# Schematic.net
KiCad netlist of a schematic drawn in EAGLE
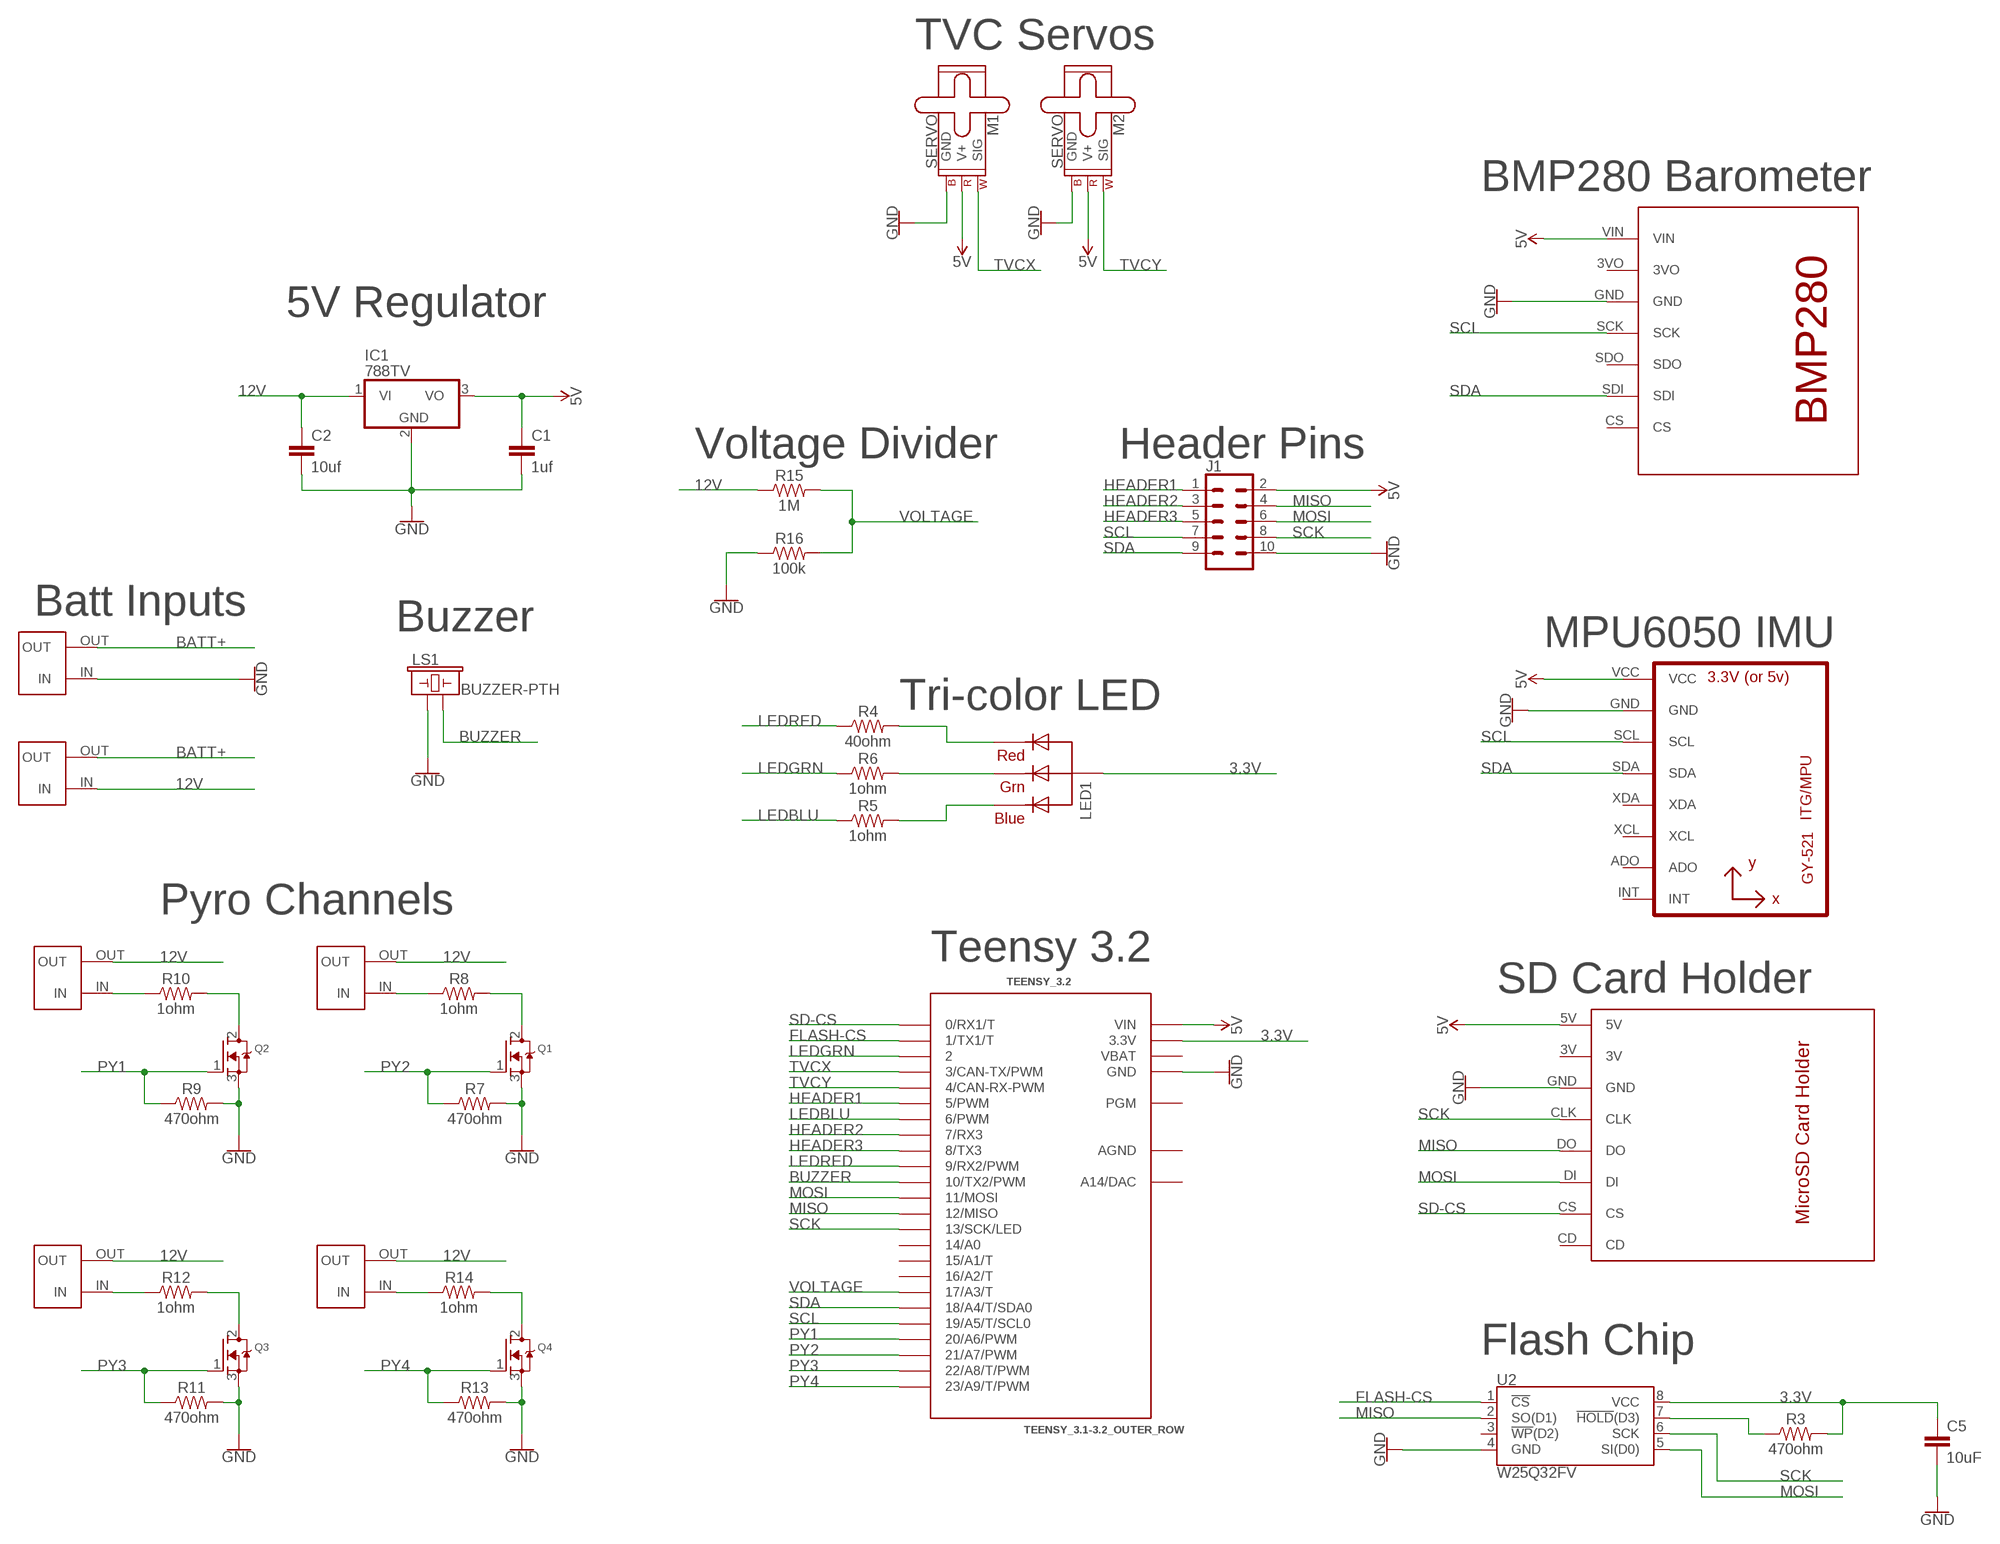
[diagram p0: schematic, sheet 1]

(export (version "E")
  (design (tool "Eeschema 10.0.6"))
  (components
    (comp (ref "C1")
      (value "1uf")
      (footprint "eagle-import:CAP-PTH-2.54")
      (libsource (lib "eagle-import") (part "22PF-PTH-2.54MM-200V-5%"))
    )
    (comp (ref "C2")
      (value "10uf")
      (footprint "eagle-import:CAP-PTH-2.54")
      (libsource (lib "eagle-import") (part "22PF-PTH-2.54MM-200V-5%"))
    )
    (comp (ref "C5")
      (value "10uF")
      (footprint "eagle-import:CAP-PTH-2.54")
      (libsource (lib "eagle-import") (part "22PF-PTH-2.54MM-200V-5%"))
    )
    (comp (ref "IC1")
      (value "788TV")
      (footprint "eagle-import:TO220V")
      (libsource (lib "eagle-import") (part "78TV8"))
    )
    (comp (ref "J1")
      (value "CONN_05X2NO_SILK")
      (footprint "eagle-import:2X5_NOSILK")
      (libsource (lib "eagle-import") (part "CONN_05X2NO_SILK"))
    )
    (comp (ref "LED1")
      (value "RGBLED_CA-5MM")
      (footprint "eagle-import:LED5MMRGB")
      (libsource (lib "eagle-import") (part "RGBLED_CA-5MM"))
    )
    (comp (ref "LS1")
      (value "BUZZER-PTH")
      (footprint "eagle-import:BUZZER-12MM")
      (libsource (lib "eagle-import") (part "BUZZER-PTH"))
    )
    (comp (ref "M1")
      (value "SERVO")
      (footprint "eagle-import:1X03")
      (libsource (lib "eagle-import") (part "SERVO"))
    )
    (comp (ref "M2")
      (value "SERVO")
      (footprint "eagle-import:1X03")
      (libsource (lib "eagle-import") (part "SERVO"))
    )
    (comp (ref "Q1")
      (value "MOSFET-NGDS_TO220V")
      (footprint "eagle-import:TO220V")
      (libsource (lib "eagle-import") (part "MOSFET-NGDS_TO220V"))
    )
    (comp (ref "Q2")
      (value "MOSFET-NGDS_TO220V")
      (footprint "eagle-import:TO220V")
      (libsource (lib "eagle-import") (part "MOSFET-NGDS_TO220V"))
    )
    (comp (ref "Q3")
      (value "MOSFET-NGDS_TO220V")
      (footprint "eagle-import:TO220V")
      (libsource (lib "eagle-import") (part "MOSFET-NGDS_TO220V"))
    )
    (comp (ref "Q4")
      (value "MOSFET-NGDS_TO220V")
      (footprint "eagle-import:TO220V")
      (libsource (lib "eagle-import") (part "MOSFET-NGDS_TO220V"))
    )
    (comp (ref "R3")
      (value "470ohm")
      (footprint "eagle-import:AXIAL-0.3")
      (libsource (lib "eagle-import") (part "10MOHM-HORIZ-1/4W-5%"))
    )
    (comp (ref "R4")
      (value "40ohm")
      (footprint "eagle-import:AXIAL-0.3")
      (libsource (lib "eagle-import") (part "10MOHM-HORIZ-1/4W-5%"))
    )
    (comp (ref "R5")
      (value "1ohm")
      (footprint "eagle-import:AXIAL-0.3")
      (libsource (lib "eagle-import") (part "10MOHM-HORIZ-1/4W-5%"))
    )
    (comp (ref "R6")
      (value "1ohm")
      (footprint "eagle-import:AXIAL-0.3")
      (libsource (lib "eagle-import") (part "10MOHM-HORIZ-1/4W-5%"))
    )
    (comp (ref "R7")
      (value "470ohm")
      (footprint "eagle-import:AXIAL-0.3")
      (libsource (lib "eagle-import") (part "10MOHM-HORIZ-1/4W-5%"))
    )
    (comp (ref "R8")
      (value "1ohm")
      (footprint "eagle-import:AXIAL-0.3")
      (libsource (lib "eagle-import") (part "10MOHM-HORIZ-1/4W-5%"))
    )
    (comp (ref "R9")
      (value "470ohm")
      (footprint "eagle-import:AXIAL-0.3")
      (libsource (lib "eagle-import") (part "10MOHM-HORIZ-1/4W-5%"))
    )
    (comp (ref "R10")
      (value "1ohm")
      (footprint "eagle-import:AXIAL-0.3")
      (libsource (lib "eagle-import") (part "10MOHM-HORIZ-1/4W-5%"))
    )
    (comp (ref "R11")
      (value "470ohm")
      (footprint "eagle-import:AXIAL-0.3")
      (libsource (lib "eagle-import") (part "10MOHM-HORIZ-1/4W-5%"))
    )
    (comp (ref "R12")
      (value "1ohm")
      (footprint "eagle-import:AXIAL-0.3")
      (libsource (lib "eagle-import") (part "10MOHM-HORIZ-1/4W-5%"))
    )
    (comp (ref "R13")
      (value "470ohm")
      (footprint "eagle-import:AXIAL-0.3")
      (libsource (lib "eagle-import") (part "10MOHM-HORIZ-1/4W-5%"))
    )
    (comp (ref "R14")
      (value "1ohm")
      (footprint "eagle-import:AXIAL-0.3")
      (libsource (lib "eagle-import") (part "10MOHM-HORIZ-1/4W-5%"))
    )
    (comp (ref "R15")
      (value "1M")
      (footprint "eagle-import:AXIAL-0.3")
      (libsource (lib "eagle-import") (part "10MOHM-HORIZ-1/4W-5%"))
    )
    (comp (ref "R16")
      (value "100k")
      (footprint "eagle-import:AXIAL-0.3")
      (libsource (lib "eagle-import") (part "10MOHM-HORIZ-1/4W-5%"))
    )
    (comp (ref "TEENSY_3.2")
      (value "TEENSY_3.1-3.2_OUTER_ROW")
      (footprint "eagle-import:TEENSY_3.0-3.2&LC_OUTER_ROW")
      (libsource (lib "eagle-import") (part "TEENSY_3.1-3.2_OUTER_ROW"))
    )
    (comp (ref "U$2")
      (value "BMP280")
      (footprint "eagle-import:BMP280")
      (libsource (lib "eagle-import") (part "BMP280"))
    )
    (comp (ref "U$3")
      (value "MICROSDCARDHOLDER")
      (footprint "eagle-import:SDCARDHOLDER")
      (libsource (lib "eagle-import") (part "MICROSDCARDHOLDER"))
    )
    (comp (ref "U$4")
      (value "BLACKTERMBLOCK")
      (footprint "eagle-import:BLACKTERMBLOCK")
      (libsource (lib "eagle-import") (part "BLACKTERMBLOCK"))
    )
    (comp (ref "U$5")
      (value "BLACKTERMBLOCK")
      (footprint "eagle-import:BLACKTERMBLOCK")
      (libsource (lib "eagle-import") (part "BLACKTERMBLOCK"))
    )
    (comp (ref "U$6")
      (value "BLACKTERMBLOCK")
      (footprint "eagle-import:BLACKTERMBLOCK")
      (libsource (lib "eagle-import") (part "BLACKTERMBLOCK"))
    )
    (comp (ref "U$7")
      (value "BLACKTERMBLOCK")
      (footprint "eagle-import:BLACKTERMBLOCK")
      (libsource (lib "eagle-import") (part "BLACKTERMBLOCK"))
    )
    (comp (ref "U$8")
      (value "BLACKTERMBLOCK")
      (footprint "eagle-import:BLACKTERMBLOCK")
      (libsource (lib "eagle-import") (part "BLACKTERMBLOCK"))
    )
    (comp (ref "U$9")
      (value "BLACKTERMBLOCK")
      (footprint "eagle-import:BLACKTERMBLOCK")
      (libsource (lib "eagle-import") (part "BLACKTERMBLOCK"))
    )
    (comp (ref "U1")
      (value "GY-521MPU6050")
      (footprint "eagle-import:GY-521")
      (libsource (lib "eagle-import") (part "GY-521MPU6050"))
    )
    (comp (ref "U2")
      (value "W25Q32FV")
      (footprint "eagle-import:SOIC-8")
      (libsource (lib "eagle-import") (part "W25Q32FVSS"))
    )
  )
  (nets
    (net (code "1") (name "/3.3V") (class "Default")
      (node (ref "C5") (pin "1") (pinfunction "1_1") (pintype "passive"))
      (node (ref "LED1") (pin "2") (pinfunction "VCC_2") (pintype "bidirectional"))
      (node (ref "R3") (pin "P$2") (pinfunction "2_P$2") (pintype "passive"))
      (node (ref "TEENSY_3.2") (pin "3.3V") (pinfunction "3.3V_3.3V") (pintype "power_in"))
      (node (ref "TEENSY_3.2") (pin "3.3V1") (pinfunction "3.3V_3.3V1") (pintype "power_in"))
      (node (ref "U2") (pin "8") (pinfunction "VCC_8") (pintype "bidirectional"))
    )
    (net (code "2") (name "/12V") (class "Default")
      (node (ref "C2") (pin "1") (pinfunction "1_1") (pintype "passive"))
      (node (ref "IC1") (pin "1") (pinfunction "VI_1") (pintype "input"))
      (node (ref "R15") (pin "P$1") (pinfunction "1_P$1") (pintype "passive"))
      (node (ref "U$4") (pin "OUT") (pinfunction "OUT_OUT") (pintype "bidirectional"))
      (node (ref "U$5") (pin "OUT") (pinfunction "OUT_OUT") (pintype "bidirectional"))
      (node (ref "U$6") (pin "OUT") (pinfunction "OUT_OUT") (pintype "bidirectional"))
      (node (ref "U$7") (pin "OUT") (pinfunction "OUT_OUT") (pintype "bidirectional"))
      (node (ref "U$9") (pin "IN") (pinfunction "IN_IN") (pintype "bidirectional"))
    )
    (net (code "3") (name "/AGND") (class "Default")
      (node (ref "TEENSY_3.2") (pin "AGND") (pinfunction "AGND_AGND") (pintype "power_in"))
    )
    (net (code "4") (name "/BATT+") (class "Default")
      (node (ref "U$8") (pin "OUT") (pinfunction "OUT_OUT") (pintype "bidirectional"))
      (node (ref "U$9") (pin "OUT") (pinfunction "OUT_OUT") (pintype "bidirectional"))
    )
    (net (code "5") (name "/BUZZER") (class "Default")
      (node (ref "LS1") (pin "-") (pinfunction "2_-") (pintype "passive"))
      (node (ref "TEENSY_3.2") (pin "10") (pinfunction "10/TX2/PWM_10") (pintype "bidirectional"))
    )
    (net (code "6") (name "/FLASH-CS") (class "Default")
      (node (ref "TEENSY_3.2") (pin "1") (pinfunction "1/TX1/T_1") (pintype "bidirectional"))
      (node (ref "U2") (pin "1") (pinfunction "~{CS}_1") (pintype "bidirectional"))
    )
    (net (code "7") (name "/HEADER1") (class "Default")
      (node (ref "J1") (pin "1") (pinfunction "1_1") (pintype "passive"))
      (node (ref "TEENSY_3.2") (pin "5") (pinfunction "5/PWM_5") (pintype "bidirectional"))
    )
    (net (code "8") (name "/HEADER2") (class "Default")
      (node (ref "J1") (pin "3") (pinfunction "3_3") (pintype "passive"))
      (node (ref "TEENSY_3.2") (pin "7") (pinfunction "7/RX3_7") (pintype "bidirectional"))
    )
    (net (code "9") (name "/HEADER3") (class "Default")
      (node (ref "J1") (pin "5") (pinfunction "5_5") (pintype "passive"))
      (node (ref "TEENSY_3.2") (pin "8") (pinfunction "8/TX3_8") (pintype "bidirectional"))
    )
    (net (code "10") (name "/LEDBLU") (class "Default")
      (node (ref "R5") (pin "P$1") (pinfunction "1_P$1") (pintype "passive"))
      (node (ref "TEENSY_3.2") (pin "6") (pinfunction "6/PWM_6") (pintype "bidirectional"))
    )
    (net (code "11") (name "/LEDGRN") (class "Default")
      (node (ref "R6") (pin "P$1") (pinfunction "1_P$1") (pintype "passive"))
      (node (ref "TEENSY_3.2") (pin "2") (pinfunction "2_2") (pintype "bidirectional"))
    )
    (net (code "12") (name "/LEDRED") (class "Default")
      (node (ref "R4") (pin "P$1") (pinfunction "1_P$1") (pintype "passive"))
      (node (ref "TEENSY_3.2") (pin "9") (pinfunction "9/RX2/PWM_9") (pintype "bidirectional"))
    )
    (net (code "13") (name "/MISO") (class "Default")
      (node (ref "J1") (pin "4") (pinfunction "4_4") (pintype "passive"))
      (node (ref "TEENSY_3.2") (pin "12") (pinfunction "12/MISO_12") (pintype "bidirectional"))
      (node (ref "U$3") (pin "DO") (pinfunction "DO_DO") (pintype "bidirectional"))
      (node (ref "U2") (pin "2") (pinfunction "SO(D1)_2") (pintype "bidirectional"))
    )
    (net (code "14") (name "/MOSI") (class "Default")
      (node (ref "J1") (pin "6") (pinfunction "6_6") (pintype "passive"))
      (node (ref "TEENSY_3.2") (pin "11") (pinfunction "11/MOSI_11") (pintype "bidirectional"))
      (node (ref "U$3") (pin "DI") (pinfunction "DI_DI") (pintype "bidirectional"))
      (node (ref "U2") (pin "5") (pinfunction "SI(D0)_5") (pintype "bidirectional"))
    )
    (net (code "15") (name "/PY1") (class "Default")
      (node (ref "Q2") (pin "1") (pinfunction "G_1") (pintype "bidirectional"))
      (node (ref "R9") (pin "P$1") (pinfunction "1_P$1") (pintype "passive"))
      (node (ref "TEENSY_3.2") (pin "20/A6") (pinfunction "20/A6/PWM_20/A6") (pintype "bidirectional"))
    )
    (net (code "16") (name "/PY2") (class "Default")
      (node (ref "Q1") (pin "1") (pinfunction "G_1") (pintype "bidirectional"))
      (node (ref "R7") (pin "P$1") (pinfunction "1_P$1") (pintype "passive"))
      (node (ref "TEENSY_3.2") (pin "21/A7") (pinfunction "21/A7/PWM_21/A7") (pintype "bidirectional"))
    )
    (net (code "17") (name "/PY3") (class "Default")
      (node (ref "Q3") (pin "1") (pinfunction "G_1") (pintype "bidirectional"))
      (node (ref "R11") (pin "P$1") (pinfunction "1_P$1") (pintype "passive"))
      (node (ref "TEENSY_3.2") (pin "22/A8") (pinfunction "22/A8/T/PWM_22/A8") (pintype "bidirectional"))
    )
    (net (code "18") (name "/PY4") (class "Default")
      (node (ref "Q4") (pin "1") (pinfunction "G_1") (pintype "bidirectional"))
      (node (ref "R13") (pin "P$1") (pinfunction "1_P$1") (pintype "passive"))
      (node (ref "TEENSY_3.2") (pin "23/A9") (pinfunction "23/A9/T/PWM_23/A9") (pintype "bidirectional"))
    )
    (net (code "19") (name "/SCK") (class "Default")
      (node (ref "J1") (pin "8") (pinfunction "8_8") (pintype "passive"))
      (node (ref "TEENSY_3.2") (pin "13") (pinfunction "13/SCK/LED_13") (pintype "bidirectional"))
      (node (ref "U$3") (pin "CLK") (pinfunction "CLK_CLK") (pintype "bidirectional"))
      (node (ref "U2") (pin "6") (pinfunction "SCK_6") (pintype "bidirectional"))
    )
    (net (code "20") (name "/SCL") (class "Default")
      (node (ref "J1") (pin "7") (pinfunction "7_7") (pintype "passive"))
      (node (ref "TEENSY_3.2") (pin "19/A5") (pinfunction "19/A5/T/SCL0_19/A5") (pintype "bidirectional"))
      (node (ref "U$2") (pin "SCK") (pinfunction "SCK_SCK") (pintype "bidirectional"))
      (node (ref "U1") (pin "SCL") (pinfunction "SCL_SCL") (pintype "bidirectional"))
    )
    (net (code "21") (name "/SD-CS") (class "Default")
      (node (ref "TEENSY_3.2") (pin "0") (pinfunction "0/RX1/T_0") (pintype "bidirectional"))
      (node (ref "U$3") (pin "CS") (pinfunction "CS_CS") (pintype "bidirectional"))
    )
    (net (code "22") (name "/SDA") (class "Default")
      (node (ref "J1") (pin "9") (pinfunction "9_9") (pintype "passive"))
      (node (ref "TEENSY_3.2") (pin "18/A4") (pinfunction "18/A4/T/SDA0_18/A4") (pintype "bidirectional"))
      (node (ref "U$2") (pin "SDI") (pinfunction "SDI_SDI") (pintype "bidirectional"))
      (node (ref "U1") (pin "SDA") (pinfunction "SDA_SDA") (pintype "bidirectional"))
    )
    (net (code "23") (name "/TVCX") (class "Default")
      (node (ref "M1") (pin "1") (pinfunction "SIG_1") (pintype "bidirectional"))
      (node (ref "TEENSY_3.2") (pin "3") (pinfunction "3/CAN-TX/PWM_3") (pintype "bidirectional"))
    )
    (net (code "24") (name "/TVCY") (class "Default")
      (node (ref "M2") (pin "1") (pinfunction "SIG_1") (pintype "bidirectional"))
      (node (ref "TEENSY_3.2") (pin "4") (pinfunction "4/CAN-RX-PWM_4") (pintype "bidirectional"))
    )
    (net (code "25") (name "/VBAT") (class "Default")
      (node (ref "TEENSY_3.2") (pin "VBAT") (pinfunction "VBAT_VBAT") (pintype "power_in"))
    )
    (net (code "26") (name "/VOLTAGE") (class "Default")
      (node (ref "R15") (pin "P$2") (pinfunction "2_P$2") (pintype "passive"))
      (node (ref "R16") (pin "P$2") (pinfunction "2_P$2") (pintype "passive"))
      (node (ref "TEENSY_3.2") (pin "17/A3") (pinfunction "17/A3/T_17/A3") (pintype "bidirectional"))
    )
    (net (code "27") (name "5V") (class "Default")
      (node (ref "C1") (pin "1") (pinfunction "1_1") (pintype "passive"))
      (node (ref "IC1") (pin "3") (pinfunction "VO_3") (pintype "passive"))
      (node (ref "J1") (pin "2") (pinfunction "2_2") (pintype "passive"))
      (node (ref "M1") (pin "2") (pinfunction "V+_2") (pintype "bidirectional"))
      (node (ref "M2") (pin "2") (pinfunction "V+_2") (pintype "bidirectional"))
      (node (ref "TEENSY_3.2") (pin "VIN") (pinfunction "VIN_VIN") (pintype "power_in"))
      (node (ref "U$2") (pin "VIN") (pinfunction "VIN_VIN") (pintype "bidirectional"))
      (node (ref "U$3") (pin "5V") (pinfunction "5V_5V") (pintype "bidirectional"))
      (node (ref "U1") (pin "VCC") (pinfunction "VCC_VCC") (pintype "bidirectional"))
    )
    (net (code "28") (name "GND") (class "Default")
      (node (ref "C1") (pin "2") (pinfunction "2_2") (pintype "passive"))
      (node (ref "C2") (pin "2") (pinfunction "2_2") (pintype "passive"))
      (node (ref "C5") (pin "2") (pinfunction "2_2") (pintype "passive"))
      (node (ref "IC1") (pin "2") (pinfunction "GND_2") (pintype "passive"))
      (node (ref "J1") (pin "10") (pinfunction "10_10") (pintype "passive"))
      (node (ref "LS1") (pin "+") (pinfunction "1_+") (pintype "passive"))
      (node (ref "M1") (pin "3") (pinfunction "GND_3") (pintype "bidirectional"))
      (node (ref "M2") (pin "3") (pinfunction "GND_3") (pintype "bidirectional"))
      (node (ref "Q1") (pin "3") (pinfunction "S_3") (pintype "bidirectional"))
      (node (ref "Q2") (pin "3") (pinfunction "S_3") (pintype "bidirectional"))
      (node (ref "Q3") (pin "3") (pinfunction "S_3") (pintype "bidirectional"))
      (node (ref "Q4") (pin "3") (pinfunction "S_3") (pintype "bidirectional"))
      (node (ref "R11") (pin "P$2") (pinfunction "2_P$2") (pintype "passive"))
      (node (ref "R13") (pin "P$2") (pinfunction "2_P$2") (pintype "passive"))
      (node (ref "R16") (pin "P$1") (pinfunction "1_P$1") (pintype "passive"))
      (node (ref "R7") (pin "P$2") (pinfunction "2_P$2") (pintype "passive"))
      (node (ref "R9") (pin "P$2") (pinfunction "2_P$2") (pintype "passive"))
      (node (ref "TEENSY_3.2") (pin "GND") (pinfunction "GND_GND") (pintype "power_in"))
      (node (ref "TEENSY_3.2") (pin "GND1") (pinfunction "GND_GND1") (pintype "power_in"))
      (node (ref "U$2") (pin "GND") (pinfunction "GND_GND") (pintype "bidirectional"))
      (node (ref "U$3") (pin "GND") (pinfunction "GND_GND") (pintype "bidirectional"))
      (node (ref "U$8") (pin "IN") (pinfunction "IN_IN") (pintype "bidirectional"))
      (node (ref "U1") (pin "GND") (pinfunction "GND_GND") (pintype "bidirectional"))
      (node (ref "U2") (pin "4") (pinfunction "GND_4") (pintype "bidirectional"))
    )
    (net (code "29") (name "Net-(LED1-BLUE)") (class "Default")
      (node (ref "LED1") (pin "4") (pinfunction "BLUE_4") (pintype "bidirectional"))
      (node (ref "R5") (pin "P$2") (pinfunction "2_P$2") (pintype "passive"))
    )
    (net (code "30") (name "Net-(LED1-GREEN)") (class "Default")
      (node (ref "LED1") (pin "3") (pinfunction "GREEN_3") (pintype "bidirectional"))
      (node (ref "R6") (pin "P$2") (pinfunction "2_P$2") (pintype "passive"))
    )
    (net (code "31") (name "Net-(LED1-RED)") (class "Default")
      (node (ref "LED1") (pin "1") (pinfunction "RED_1") (pintype "bidirectional"))
      (node (ref "R4") (pin "P$2") (pinfunction "2_P$2") (pintype "passive"))
    )
    (net (code "32") (name "Net-(Q1-D)") (class "Default")
      (node (ref "Q1") (pin "2") (pinfunction "D_2") (pintype "bidirectional"))
      (node (ref "R8") (pin "P$2") (pinfunction "2_P$2") (pintype "passive"))
    )
    (net (code "33") (name "Net-(Q2-D)") (class "Default")
      (node (ref "Q2") (pin "2") (pinfunction "D_2") (pintype "bidirectional"))
      (node (ref "R10") (pin "P$2") (pinfunction "2_P$2") (pintype "passive"))
    )
    (net (code "34") (name "Net-(Q3-D)") (class "Default")
      (node (ref "Q3") (pin "2") (pinfunction "D_2") (pintype "bidirectional"))
      (node (ref "R12") (pin "P$2") (pinfunction "2_P$2") (pintype "passive"))
    )
    (net (code "35") (name "Net-(Q4-D)") (class "Default")
      (node (ref "Q4") (pin "2") (pinfunction "D_2") (pintype "bidirectional"))
      (node (ref "R14") (pin "P$2") (pinfunction "2_P$2") (pintype "passive"))
    )
    (net (code "36") (name "Net-(R3-1)") (class "Default")
      (node (ref "R3") (pin "P$1") (pinfunction "1_P$1") (pintype "passive"))
      (node (ref "U2") (pin "7") (pinfunction "~{HOLD}(D3)_7") (pintype "bidirectional"))
    )
    (net (code "37") (name "Net-(R8-1)") (class "Default")
      (node (ref "R8") (pin "P$1") (pinfunction "1_P$1") (pintype "passive"))
      (node (ref "U$4") (pin "IN") (pinfunction "IN_IN") (pintype "bidirectional"))
    )
    (net (code "38") (name "Net-(R10-1)") (class "Default")
      (node (ref "R10") (pin "P$1") (pinfunction "1_P$1") (pintype "passive"))
      (node (ref "U$5") (pin "IN") (pinfunction "IN_IN") (pintype "bidirectional"))
    )
    (net (code "39") (name "Net-(R12-1)") (class "Default")
      (node (ref "R12") (pin "P$1") (pinfunction "1_P$1") (pintype "passive"))
      (node (ref "U$6") (pin "IN") (pinfunction "IN_IN") (pintype "bidirectional"))
    )
    (net (code "40") (name "Net-(R14-1)") (class "Default")
      (node (ref "R14") (pin "P$1") (pinfunction "1_P$1") (pintype "passive"))
      (node (ref "U$7") (pin "IN") (pinfunction "IN_IN") (pintype "bidirectional"))
    )
    (net (code "41") (name "unconnected-(TEENSY_3.2-15{slash}A1{slash}T-Pad15{slash}A1)") (class "Default")
      (node (ref "TEENSY_3.2") (pin "15/A1") (pinfunction "15/A1/T_15/A1") (pintype "bidirectional"))
    )
    (net (code "42") (name "unconnected-(TEENSY_3.2-16{slash}A2{slash}T-Pad16{slash}A2)") (class "Default")
      (node (ref "TEENSY_3.2") (pin "16/A2") (pinfunction "16/A2/T_16/A2") (pintype "bidirectional"))
    )
    (net (code "43") (name "unconnected-(TEENSY_3.2-A14{slash}DAC-PadRESET{slash}DAC)") (class "Default")
      (node (ref "TEENSY_3.2") (pin "RESET/DAC") (pinfunction "A14/DAC_RESET/DAC") (pintype "bidirectional"))
    )
    (net (code "44") (name "unconnected-(TEENSY_3.2-Pad14{slash}A0)") (class "Default")
      (node (ref "TEENSY_3.2") (pin "14/A0") (pinfunction "14/A0_14/A0") (pintype "bidirectional"))
    )
    (net (code "45") (name "unconnected-(TEENSY_3.2-PadPGM)") (class "Default")
      (node (ref "TEENSY_3.2") (pin "PGM") (pinfunction "PGM_PGM") (pintype "bidirectional"))
    )
    (net (code "46") (name "unconnected-(U$2-Pad3VO)") (class "Default")
      (node (ref "U$2") (pin "3VO") (pinfunction "3VO_3VO") (pintype "bidirectional"))
    )
    (net (code "47") (name "unconnected-(U$2-PadCS)") (class "Default")
      (node (ref "U$2") (pin "CS") (pinfunction "CS_CS") (pintype "bidirectional"))
    )
    (net (code "48") (name "unconnected-(U$2-PadSDO)") (class "Default")
      (node (ref "U$2") (pin "SDO") (pinfunction "SDO_SDO") (pintype "bidirectional"))
    )
    (net (code "49") (name "unconnected-(U$3-Pad3V)") (class "Default")
      (node (ref "U$3") (pin "3V") (pinfunction "3V_3V") (pintype "bidirectional"))
    )
    (net (code "50") (name "unconnected-(U$3-PadCD)") (class "Default")
      (node (ref "U$3") (pin "CD") (pinfunction "CD_CD") (pintype "bidirectional"))
    )
    (net (code "51") (name "unconnected-(U1-PadADO)") (class "Default")
      (node (ref "U1") (pin "ADO") (pinfunction "ADO_ADO") (pintype "bidirectional"))
    )
    (net (code "52") (name "unconnected-(U1-PadINT)") (class "Default")
      (node (ref "U1") (pin "INT") (pinfunction "INT_INT") (pintype "bidirectional"))
    )
    (net (code "53") (name "unconnected-(U1-PadXCL)") (class "Default")
      (node (ref "U1") (pin "XCL") (pinfunction "XCL_XCL") (pintype "bidirectional"))
    )
    (net (code "54") (name "unconnected-(U1-PadXDA)") (class "Default")
      (node (ref "U1") (pin "XDA") (pinfunction "XDA_XDA") (pintype "bidirectional"))
    )
    (net (code "55") (name "unconnected-(U2-~{WP}(D2)-Pad3)") (class "Default")
      (node (ref "U2") (pin "3") (pinfunction "~{WP}(D2)_3") (pintype "bidirectional"))
    )
  )
)
